# LDOConverter_Sheet.net
KiCad netlist of a schematic drawn in Altium Designer
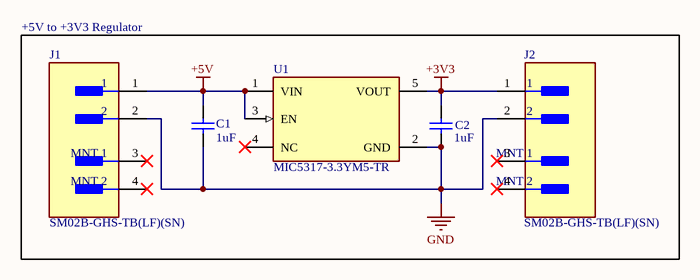
[diagram p0: LDOConverter_Sheet.SchDoc]

(export (version "E")
  (design (tool "Eeschema 10.0.6"))
  (components
    (comp (ref "C1")
      (value "1uF")
      (footprint "CAPC2013X145X50LL20T20")
      (fields (field (name "PART NUMBER") "VJ0805Y105JXQTW1BC") (field (name "MANUFACTURER") "Vitramon"))
      (libsource (lib "Altium Content Vault") (part "CAP"))
    )
    (comp (ref "C2")
      (value "1uF")
      (footprint "CAPC2013X145X50LL20T20")
      (fields (field (name "PART NUMBER") "VJ0805Y105JXQTW1BC") (field (name "MANUFACTURER") "Vitramon"))
      (libsource (lib "Altium Content Vault") (part "CAP"))
    )
    (comp (ref "J1")
      (value "SM02B-GHS-TB(LF)(SN)")
      (footprint "FP-SM02B-GHS-TB_LF_SN-MFG")
      (description "CONN HEADER SMD R/A 2POS 1.25MM")
      (libsource (lib "") (part "56ec3178a87b3978bdc1b3682cd516a_1"))
    )
    (comp (ref "J2")
      (value "SM02B-GHS-TB(LF)(SN)")
      (footprint "FP-SM02B-GHS-TB_LF_SN-MFG")
      (description "CONN HEADER SMD R/A 2POS 1.25MM")
      (libsource (lib "Altium Content Vault") (part "56ec3178a87b3978bdc1b3682cd516a"))
    )
    (comp (ref "U1")
      (value "MIC5317-3.3YM5-TR")
      (footprint "FP-SOT23-5LD-PL-1-MFG")
      (description "IC REG LINEAR 3.3V 150MA SOT23-5")
      (libsource (lib "Altium Content Vault") (part "0a093dae7315cdc977fd108dde87457"))
    )
  )
  (nets
    (net (code "1") (name "+3V3") (class "Default")
      (node (ref "C2") (pin "2") (pinfunction "2_2") (pintype "passive"))
      (node (ref "J2") (pin "1") (pinfunction "1_1") (pintype "passive"))
      (node (ref "U1") (pin "5") (pinfunction "VOUT_5") (pintype "power_in"))
    )
    (net (code "2") (name "+5V") (class "Default")
      (node (ref "C1") (pin "2") (pinfunction "2_2") (pintype "passive"))
      (node (ref "J1") (pin "1") (pinfunction "1_1") (pintype "passive"))
      (node (ref "U1") (pin "1") (pinfunction "VIN_1") (pintype "power_in"))
      (node (ref "U1") (pin "3") (pinfunction "EN_3") (pintype "input"))
    )
    (net (code "3") (name "GND") (class "Default")
      (node (ref "C1") (pin "1") (pinfunction "1_1") (pintype "passive"))
      (node (ref "C2") (pin "1") (pinfunction "1_1") (pintype "passive"))
      (node (ref "J1") (pin "2") (pinfunction "2_2") (pintype "passive"))
      (node (ref "J2") (pin "2") (pinfunction "2_2") (pintype "passive"))
      (node (ref "U1") (pin "2") (pinfunction "GND_2") (pintype "power_in"))
    )
    (net (code "4") (name "unconnected-(J1-MNT_1-Pad3)") (class "Default")
      (node (ref "J1") (pin "3") (pinfunction "MNT_1_3") (pintype "passive+no_connect"))
    )
    (net (code "5") (name "unconnected-(J1-MNT_2-Pad4)") (class "Default")
      (node (ref "J1") (pin "4") (pinfunction "MNT_2_4") (pintype "passive+no_connect"))
    )
    (net (code "6") (name "unconnected-(J2-MNT_1-Pad3)") (class "Default")
      (node (ref "J2") (pin "3") (pinfunction "MNT_1_3") (pintype "passive+no_connect"))
    )
    (net (code "7") (name "unconnected-(J2-MNT_2-Pad4)") (class "Default")
      (node (ref "J2") (pin "4") (pinfunction "MNT_2_4") (pintype "passive+no_connect"))
    )
    (net (code "8") (name "unconnected-(U1-NC-Pad4)") (class "Default")
      (node (ref "U1") (pin "4") (pinfunction "NC_4") (pintype "passive+no_connect"))
    )
  )
)
